# 6P1_EVB.net
KiCad netlist of a schematic drawn in EAGLE
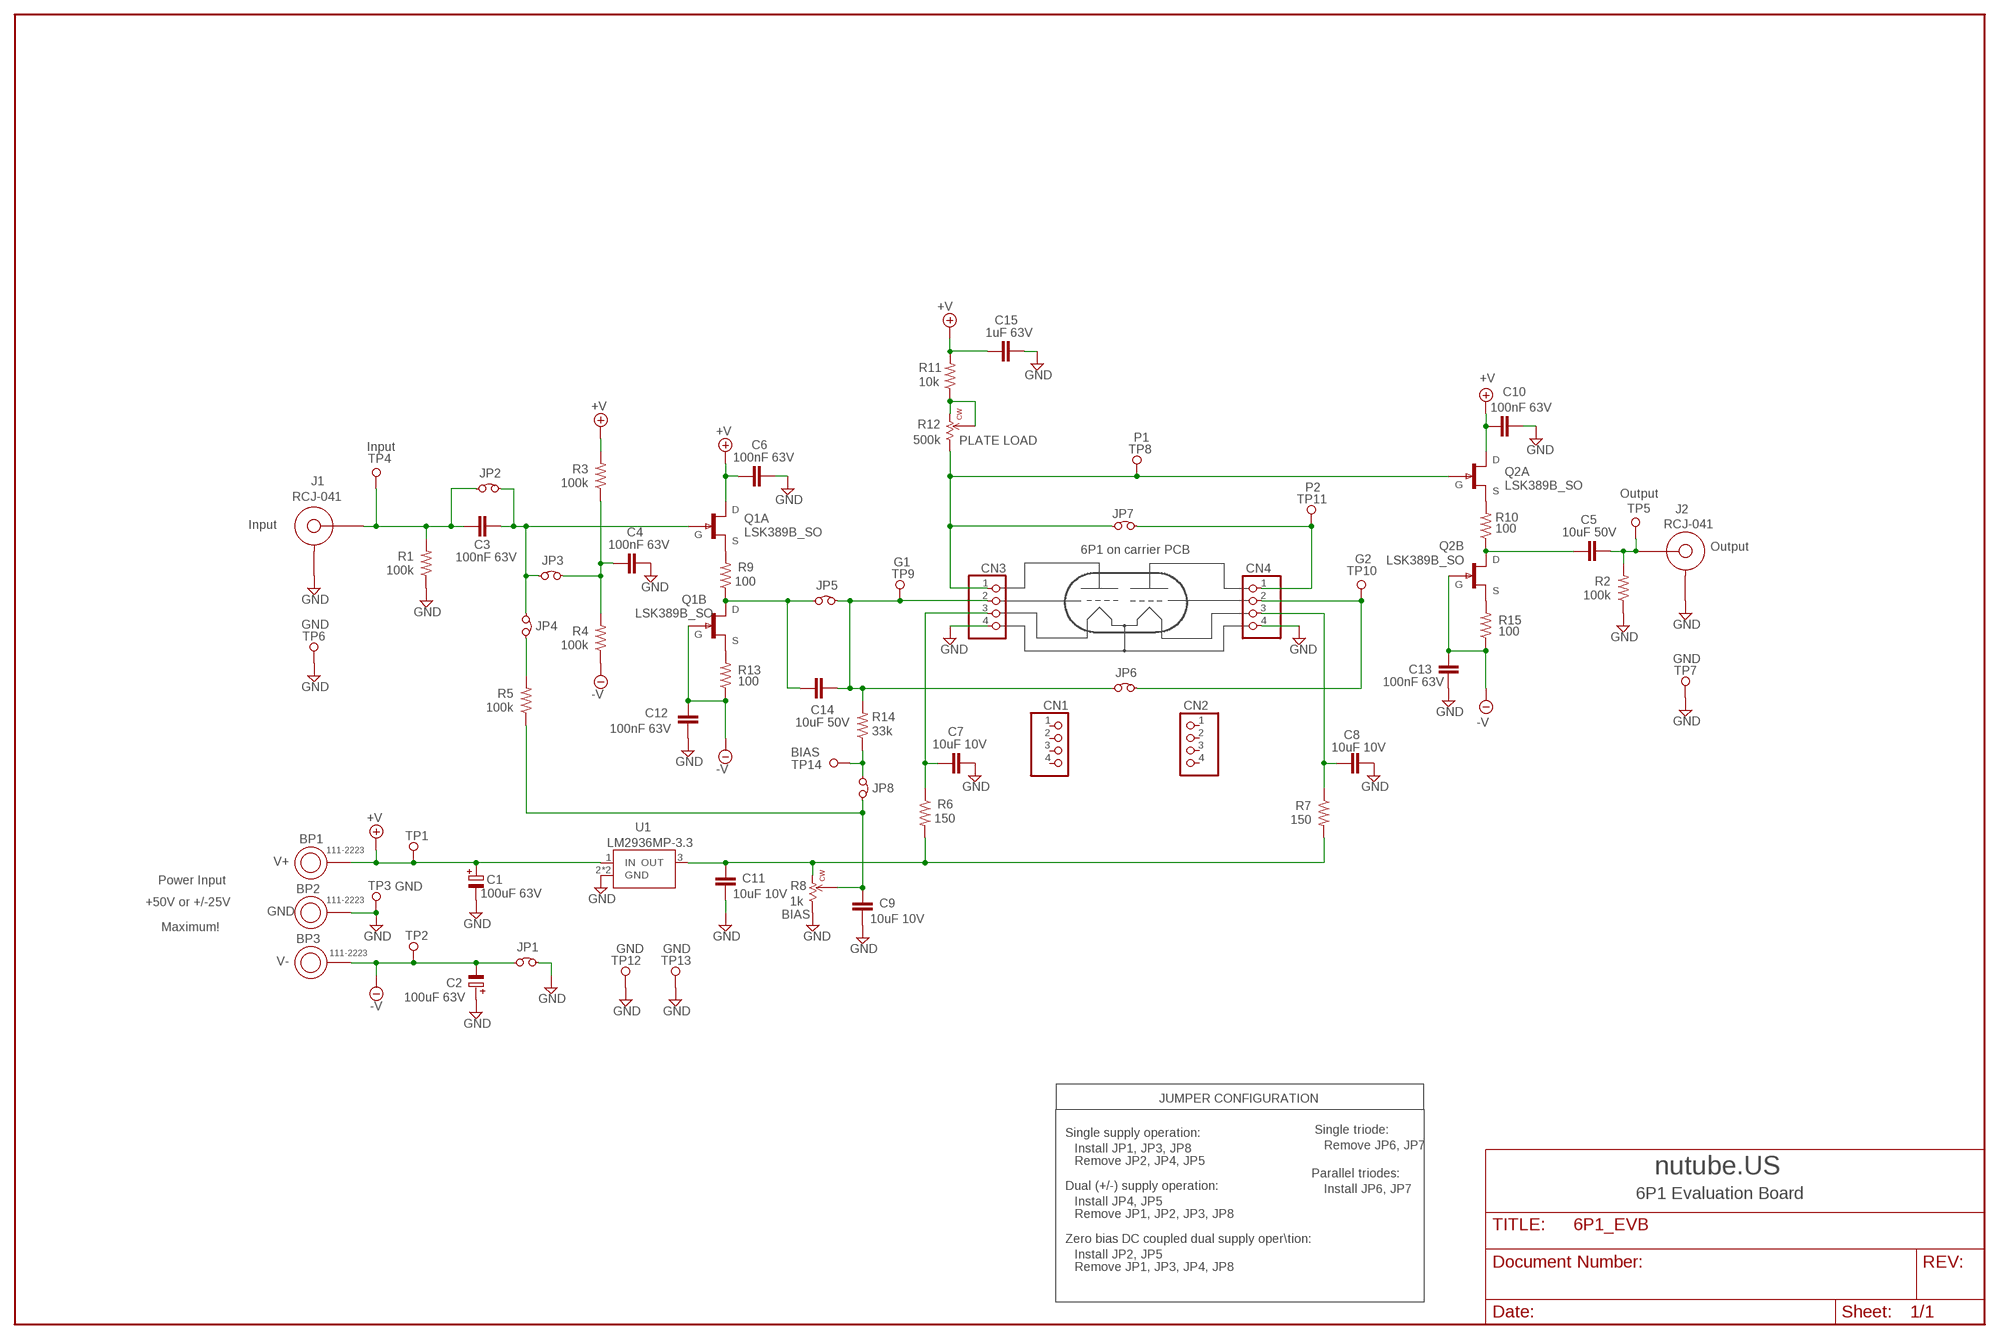
[diagram p0: schematic, sheet 1]

(export (version "E")
  (design (tool "Eeschema 10.0.6"))
  (components
    (comp (ref "BP1")
      (value "111-2223")
      (footprint "eagle-import:BANANA_BP")
      (libsource (lib "eagle-import") (part "BANANA_BP"))
    )
    (comp (ref "BP2")
      (value "111-2223")
      (footprint "eagle-import:BANANA_BP")
      (libsource (lib "eagle-import") (part "BANANA_BP"))
    )
    (comp (ref "BP3")
      (value "111-2223")
      (footprint "eagle-import:BANANA_BP")
      (libsource (lib "eagle-import") (part "BANANA_BP"))
    )
    (comp (ref "C1")
      (value "100uF 63V")
      (footprint "eagle-import:ELCAP_SMT_10MM")
      (libsource (lib "eagle-import") (part "CAP_EL_SMT_10MM"))
    )
    (comp (ref "C2")
      (value "100uF 63V")
      (footprint "eagle-import:ELCAP_SMT_10MM")
      (libsource (lib "eagle-import") (part "CAP_EL_SMT_10MM"))
    )
    (comp (ref "C3")
      (value "100nF 63V")
      (footprint "eagle-import:C050-030X075")
      (libsource (lib "eagle-import") (part "C-EU050-030X075"))
    )
    (comp (ref "C4")
      (value "100nF 63V")
      (footprint "eagle-import:C050-030X075")
      (libsource (lib "eagle-import") (part "C-EU050-030X075"))
    )
    (comp (ref "C5")
      (value "10uF 50V")
      (footprint "eagle-import:C050-110X075")
      (libsource (lib "eagle-import") (part "C-EU050-110X075"))
    )
    (comp (ref "C6")
      (value "100nF 63V")
      (footprint "eagle-import:C050-030X075")
      (libsource (lib "eagle-import") (part "C-EU050-030X075"))
    )
    (comp (ref "C7")
      (value "10uF 10V")
      (footprint "eagle-import:C1206")
      (libsource (lib "eagle-import") (part "C-EUC1206"))
    )
    (comp (ref "C8")
      (value "10uF 10V")
      (footprint "eagle-import:C1206")
      (libsource (lib "eagle-import") (part "C-EUC1206"))
    )
    (comp (ref "C9")
      (value "10uF 10V")
      (footprint "eagle-import:C1206")
      (libsource (lib "eagle-import") (part "C-EUC1206"))
    )
    (comp (ref "C10")
      (value "100nF 63V")
      (footprint "eagle-import:C050-030X075")
      (libsource (lib "eagle-import") (part "C-EU050-030X075"))
    )
    (comp (ref "C11")
      (value "10uF 10V")
      (footprint "eagle-import:C1206")
      (libsource (lib "eagle-import") (part "C-EUC1206"))
    )
    (comp (ref "C12")
      (value "100nF 63V")
      (footprint "eagle-import:C050-030X075")
      (libsource (lib "eagle-import") (part "C-EU050-030X075"))
    )
    (comp (ref "C13")
      (value "100nF 63V")
      (footprint "eagle-import:C050-030X075")
      (libsource (lib "eagle-import") (part "C-EU050-030X075"))
    )
    (comp (ref "C14")
      (value "10uF 50V")
      (footprint "eagle-import:C050-110X075")
      (libsource (lib "eagle-import") (part "C-EU050-110X075"))
    )
    (comp (ref "C15")
      (value "1uF 63V")
      (footprint "eagle-import:C050-050X075")
      (libsource (lib "eagle-import") (part "C-EU050-050X075"))
    )
    (comp (ref "CN1")
      (value "PINHD-1X4")
      (footprint "eagle-import:1X04")
      (libsource (lib "eagle-import") (part "PINHD-1X4"))
    )
    (comp (ref "CN2")
      (value "PINHD-1X4")
      (footprint "eagle-import:1X04")
      (libsource (lib "eagle-import") (part "PINHD-1X4"))
    )
    (comp (ref "CN3")
      (value "PINHD-1X4")
      (footprint "eagle-import:1X04")
      (libsource (lib "eagle-import") (part "PINHD-1X4"))
    )
    (comp (ref "CN4")
      (value "PINHD-1X4")
      (footprint "eagle-import:1X04")
      (libsource (lib "eagle-import") (part "PINHD-1X4"))
    )
    (comp (ref "J1")
      (value "RCJ-041")
      (footprint "eagle-import:JACK_RCA")
      (libsource (lib "eagle-import") (part "JACK_RCA"))
    )
    (comp (ref "J2")
      (value "RCJ-041")
      (footprint "eagle-import:JACK_RCA")
      (libsource (lib "eagle-import") (part "JACK_RCA"))
    )
    (comp (ref "JP1")
      (value "JUMPER")
      (footprint "eagle-import:HDR2X1")
      (libsource (lib "eagle-import") (part "JUMPER"))
    )
    (comp (ref "JP2")
      (value "JUMPER")
      (footprint "eagle-import:HDR2X1")
      (libsource (lib "eagle-import") (part "JUMPER"))
    )
    (comp (ref "JP3")
      (value "JUMPER")
      (footprint "eagle-import:HDR2X1")
      (libsource (lib "eagle-import") (part "JUMPER"))
    )
    (comp (ref "JP4")
      (value "JUMPER")
      (footprint "eagle-import:HDR2X1")
      (libsource (lib "eagle-import") (part "JUMPER"))
    )
    (comp (ref "JP5")
      (value "JUMPER")
      (footprint "eagle-import:HDR2X1")
      (libsource (lib "eagle-import") (part "JUMPER"))
    )
    (comp (ref "JP6")
      (value "JUMPER")
      (footprint "eagle-import:HDR2X1")
      (libsource (lib "eagle-import") (part "JUMPER"))
    )
    (comp (ref "JP7")
      (value "JUMPER")
      (footprint "eagle-import:HDR2X1")
      (libsource (lib "eagle-import") (part "JUMPER"))
    )
    (comp (ref "JP8")
      (value "JUMPER")
      (footprint "eagle-import:HDR2X1")
      (libsource (lib "eagle-import") (part "JUMPER"))
    )
    (comp (ref "Q1")
      (value "LSK389B_SO")
      (footprint "eagle-import:SO8")
      (libsource (lib "eagle-import") (part "LSK389B_SO"))
    )
    (comp (ref "Q2")
      (value "LSK389B_SO")
      (footprint "eagle-import:SO8")
      (libsource (lib "eagle-import") (part "LSK389B_SO"))
    )
    (comp (ref "R1")
      (value "100k")
      (footprint "eagle-import:R0805")
      (libsource (lib "eagle-import") (part "R-US_R0805"))
    )
    (comp (ref "R2")
      (value "100k")
      (footprint "eagle-import:R0805")
      (libsource (lib "eagle-import") (part "R-US_R0805"))
    )
    (comp (ref "R3")
      (value "100k")
      (footprint "eagle-import:R0805")
      (libsource (lib "eagle-import") (part "R-US_R0805"))
    )
    (comp (ref "R4")
      (value "100k")
      (footprint "eagle-import:R0805")
      (libsource (lib "eagle-import") (part "R-US_R0805"))
    )
    (comp (ref "R5")
      (value "100k")
      (footprint "eagle-import:R0805")
      (libsource (lib "eagle-import") (part "R-US_R0805"))
    )
    (comp (ref "R6")
      (value "150")
      (footprint "eagle-import:R0805")
      (libsource (lib "eagle-import") (part "R-US_R0805"))
    )
    (comp (ref "R7")
      (value "150")
      (footprint "eagle-import:R0805")
      (libsource (lib "eagle-import") (part "R-US_R0805"))
    )
    (comp (ref "R8")
      (value "1k")
      (footprint "eagle-import:TRIMPOT_3266")
      (libsource (lib "eagle-import") (part "TRIMPOT_3266"))
    )
    (comp (ref "R9")
      (value "100")
      (footprint "eagle-import:R0805")
      (libsource (lib "eagle-import") (part "R-US_R0805"))
    )
    (comp (ref "R10")
      (value "100")
      (footprint "eagle-import:R0805")
      (libsource (lib "eagle-import") (part "R-US_R0805"))
    )
    (comp (ref "R11")
      (value "10k")
      (footprint "eagle-import:R0805")
      (libsource (lib "eagle-import") (part "R-US_R0805"))
    )
    (comp (ref "R12")
      (value "500k")
      (footprint "eagle-import:TRIMPOT_3266")
      (libsource (lib "eagle-import") (part "TRIMPOT_3266"))
    )
    (comp (ref "R13")
      (value "100")
      (footprint "eagle-import:R0805")
      (libsource (lib "eagle-import") (part "R-US_R0805"))
    )
    (comp (ref "R14")
      (value "33k")
      (footprint "eagle-import:R0805")
      (libsource (lib "eagle-import") (part "R-US_R0805"))
    )
    (comp (ref "R15")
      (value "100")
      (footprint "eagle-import:R0805")
      (libsource (lib "eagle-import") (part "R-US_R0805"))
    )
    (comp (ref "TP1")
      (value "TESTPOINT")
      (footprint "eagle-import:TESTPOINT_63")
      (libsource (lib "eagle-import") (part "TESTPOINT"))
    )
    (comp (ref "TP2")
      (value "TESTPOINT")
      (footprint "eagle-import:TESTPOINT_63")
      (libsource (lib "eagle-import") (part "TESTPOINT"))
    )
    (comp (ref "TP3")
      (value "TESTPOINT")
      (footprint "eagle-import:TESTPOINT_63")
      (libsource (lib "eagle-import") (part "TESTPOINT"))
    )
    (comp (ref "TP4")
      (value "TESTPOINT")
      (footprint "eagle-import:TESTPOINT_63")
      (libsource (lib "eagle-import") (part "TESTPOINT"))
    )
    (comp (ref "TP5")
      (value "TESTPOINT")
      (footprint "eagle-import:TESTPOINT_63")
      (libsource (lib "eagle-import") (part "TESTPOINT"))
    )
    (comp (ref "TP6")
      (value "TESTPOINT")
      (footprint "eagle-import:TESTPOINT_63")
      (libsource (lib "eagle-import") (part "TESTPOINT"))
    )
    (comp (ref "TP7")
      (value "TESTPOINT")
      (footprint "eagle-import:TESTPOINT_63")
      (libsource (lib "eagle-import") (part "TESTPOINT"))
    )
    (comp (ref "TP8")
      (value "TESTPOINT")
      (footprint "eagle-import:TESTPOINT_63")
      (libsource (lib "eagle-import") (part "TESTPOINT"))
    )
    (comp (ref "TP9")
      (value "TESTPOINT")
      (footprint "eagle-import:TESTPOINT_63")
      (libsource (lib "eagle-import") (part "TESTPOINT"))
    )
    (comp (ref "TP10")
      (value "TESTPOINT")
      (footprint "eagle-import:TESTPOINT_63")
      (libsource (lib "eagle-import") (part "TESTPOINT"))
    )
    (comp (ref "TP11")
      (value "TESTPOINT")
      (footprint "eagle-import:TESTPOINT_63")
      (libsource (lib "eagle-import") (part "TESTPOINT"))
    )
    (comp (ref "TP12")
      (value "TESTPOINT")
      (footprint "eagle-import:TESTPOINT_63")
      (libsource (lib "eagle-import") (part "TESTPOINT"))
    )
    (comp (ref "TP13")
      (value "TESTPOINT")
      (footprint "eagle-import:TESTPOINT_63")
      (libsource (lib "eagle-import") (part "TESTPOINT"))
    )
    (comp (ref "TP14")
      (value "TESTPOINT")
      (footprint "eagle-import:TESTPOINT_63")
      (libsource (lib "eagle-import") (part "TESTPOINT"))
    )
    (comp (ref "U1")
      (value "LM2936MP-3.3")
      (footprint "eagle-import:SOT223-3")
      (libsource (lib "eagle-import") (part "LM2940S2"))
    )
  )
  (nets
    (net (code "1") (name "+V") (class "Default")
      (node (ref "BP1") (pin "P$2") (pinfunction "P$1_P$2") (pintype "passive"))
      (node (ref "C1") (pin "P$1") (pinfunction "+_P$1") (pintype "passive"))
      (node (ref "C10") (pin "2") (pinfunction "2_2") (pintype "passive"))
      (node (ref "C15") (pin "2") (pinfunction "2_2") (pintype "passive"))
      (node (ref "C6") (pin "2") (pinfunction "2_2") (pintype "passive"))
      (node (ref "Q1") (pin "2") (pinfunction "D_2") (pintype "passive"))
      (node (ref "Q2") (pin "2") (pinfunction "D_2") (pintype "passive"))
      (node (ref "R11") (pin "2") (pinfunction "2_2") (pintype "passive"))
      (node (ref "R3") (pin "2") (pinfunction "2_2") (pintype "passive"))
      (node (ref "TP1") (pin "P$1") (pinfunction "P$1_P$1") (pintype "passive"))
      (node (ref "U1") (pin "1") (pinfunction "IN_1") (pintype "passive"))
    )
    (net (code "2") (name "-V") (class "Default")
      (node (ref "BP3") (pin "P$2") (pinfunction "P$1_P$2") (pintype "passive"))
      (node (ref "C12") (pin "2") (pinfunction "2_2") (pintype "passive"))
      (node (ref "C13") (pin "2") (pinfunction "2_2") (pintype "passive"))
      (node (ref "C2") (pin "P$2") (pinfunction "-_P$2") (pintype "passive"))
      (node (ref "JP1") (pin "1") (pinfunction "1_1") (pintype "passive"))
      (node (ref "Q1") (pin "8") (pinfunction "G_8") (pintype "passive"))
      (node (ref "Q2") (pin "8") (pinfunction "G_8") (pintype "passive"))
      (node (ref "R13") (pin "1") (pinfunction "1_1") (pintype "passive"))
      (node (ref "R15") (pin "1") (pinfunction "1_1") (pintype "passive"))
      (node (ref "R4") (pin "1") (pinfunction "1_1") (pintype "passive"))
      (node (ref "TP2") (pin "P$1") (pinfunction "P$1_P$1") (pintype "passive"))
    )
    (net (code "3") (name "GND") (class "Default")
      (node (ref "BP2") (pin "P$2") (pinfunction "P$1_P$2") (pintype "passive"))
      (node (ref "C1") (pin "P$2") (pinfunction "-_P$2") (pintype "passive"))
      (node (ref "C10") (pin "1") (pinfunction "1_1") (pintype "passive"))
      (node (ref "C11") (pin "2") (pinfunction "2_2") (pintype "passive"))
      (node (ref "C12") (pin "1") (pinfunction "1_1") (pintype "passive"))
      (node (ref "C13") (pin "1") (pinfunction "1_1") (pintype "passive"))
      (node (ref "C15") (pin "1") (pinfunction "1_1") (pintype "passive"))
      (node (ref "C2") (pin "P$1") (pinfunction "+_P$1") (pintype "passive"))
      (node (ref "C4") (pin "1") (pinfunction "1_1") (pintype "passive"))
      (node (ref "C6") (pin "1") (pinfunction "1_1") (pintype "passive"))
      (node (ref "C7") (pin "2") (pinfunction "2_2") (pintype "passive"))
      (node (ref "C8") (pin "2") (pinfunction "2_2") (pintype "passive"))
      (node (ref "C9") (pin "2") (pinfunction "2_2") (pintype "passive"))
      (node (ref "CN3") (pin "4") (pinfunction "4_4") (pintype "passive"))
      (node (ref "CN4") (pin "4") (pinfunction "4_4") (pintype "passive"))
      (node (ref "J1") (pin "P$1") (pinfunction "3_P$1") (pintype "passive"))
      (node (ref "J2") (pin "P$1") (pinfunction "3_P$1") (pintype "passive"))
      (node (ref "JP1") (pin "2") (pinfunction "2_2") (pintype "passive"))
      (node (ref "R1") (pin "1") (pinfunction "1_1") (pintype "passive"))
      (node (ref "R2") (pin "1") (pinfunction "1_1") (pintype "passive"))
      (node (ref "R8") (pin "1") (pinfunction "1_1") (pintype "passive"))
      (node (ref "TP12") (pin "P$1") (pinfunction "P$1_P$1") (pintype "passive"))
      (node (ref "TP13") (pin "P$1") (pinfunction "P$1_P$1") (pintype "passive"))
      (node (ref "TP3") (pin "P$1") (pinfunction "P$1_P$1") (pintype "passive"))
      (node (ref "TP6") (pin "P$1") (pinfunction "P$1_P$1") (pintype "passive"))
      (node (ref "TP7") (pin "P$1") (pinfunction "P$1_P$1") (pintype "passive"))
      (node (ref "U1") (pin "2") (pinfunction "GND_2") (pintype "passive"))
      (node (ref "U1") (pin "4") (pinfunction "GND_4") (pintype "passive"))
    )
    (net (code "4") (name "Net-(C4-Pad2)") (class "Default")
      (node (ref "C4") (pin "2") (pinfunction "2_2") (pintype "passive"))
      (node (ref "JP3") (pin "2") (pinfunction "2_2") (pintype "passive"))
      (node (ref "R3") (pin "1") (pinfunction "1_1") (pintype "passive"))
      (node (ref "R4") (pin "2") (pinfunction "2_2") (pintype "passive"))
    )
    (net (code "5") (name "Net-(C7-Pad1)") (class "Default")
      (node (ref "C7") (pin "1") (pinfunction "1_1") (pintype "passive"))
      (node (ref "CN3") (pin "3") (pinfunction "3_3") (pintype "passive"))
      (node (ref "R6") (pin "1") (pinfunction "1_1") (pintype "passive"))
    )
    (net (code "6") (name "Net-(C8-Pad1)") (class "Default")
      (node (ref "C8") (pin "1") (pinfunction "1_1") (pintype "passive"))
      (node (ref "CN4") (pin "3") (pinfunction "3_3") (pintype "passive"))
      (node (ref "R7") (pin "1") (pinfunction "1_1") (pintype "passive"))
    )
    (net (code "7") (name "Net-(C9-Pad1)") (class "Default")
      (node (ref "C9") (pin "1") (pinfunction "1_1") (pintype "passive"))
      (node (ref "JP8") (pin "2") (pinfunction "2_2") (pintype "passive"))
      (node (ref "R5") (pin "1") (pinfunction "1_1") (pintype "passive"))
      (node (ref "R8") (pin "2") (pinfunction "2_2") (pintype "passive"))
    )
    (net (code "8") (name "Net-(C14-Pad1)") (class "Default")
      (node (ref "C14") (pin "1") (pinfunction "1_1") (pintype "passive"))
      (node (ref "CN3") (pin "2") (pinfunction "2_2") (pintype "passive"))
      (node (ref "JP5") (pin "2") (pinfunction "2_2") (pintype "passive"))
      (node (ref "JP6") (pin "1") (pinfunction "1_1") (pintype "passive"))
      (node (ref "R14") (pin "2") (pinfunction "2_2") (pintype "passive"))
      (node (ref "TP9") (pin "P$1") (pinfunction "P$1_P$1") (pintype "passive"))
    )
    (net (code "9") (name "Net-(CN4-Pad1)") (class "Default")
      (node (ref "CN4") (pin "1") (pinfunction "1_1") (pintype "passive"))
      (node (ref "JP7") (pin "2") (pinfunction "2_2") (pintype "passive"))
      (node (ref "TP11") (pin "P$1") (pinfunction "P$1_P$1") (pintype "passive"))
    )
    (net (code "10") (name "Net-(CN4-Pad2)") (class "Default")
      (node (ref "CN4") (pin "2") (pinfunction "2_2") (pintype "passive"))
      (node (ref "JP6") (pin "2") (pinfunction "2_2") (pintype "passive"))
      (node (ref "TP10") (pin "P$1") (pinfunction "P$1_P$1") (pintype "passive"))
    )
    (net (code "11") (name "Net-(J1-1)") (class "Default")
      (node (ref "C3") (pin "2") (pinfunction "2_2") (pintype "passive"))
      (node (ref "J1") (pin "P$2") (pinfunction "1_P$2") (pintype "passive"))
      (node (ref "JP2") (pin "1") (pinfunction "1_1") (pintype "passive"))
      (node (ref "R1") (pin "2") (pinfunction "2_2") (pintype "passive"))
      (node (ref "TP4") (pin "P$1") (pinfunction "P$1_P$1") (pintype "passive"))
    )
    (net (code "12") (name "Net-(J2-1)") (class "Default")
      (node (ref "C5") (pin "1") (pinfunction "1_1") (pintype "passive"))
      (node (ref "J2") (pin "P$2") (pinfunction "1_P$2") (pintype "passive"))
      (node (ref "R2") (pin "2") (pinfunction "2_2") (pintype "passive"))
      (node (ref "TP5") (pin "P$1") (pinfunction "P$1_P$1") (pintype "passive"))
    )
    (net (code "13") (name "Net-(JP4-Pad2)") (class "Default")
      (node (ref "JP4") (pin "2") (pinfunction "2_2") (pintype "passive"))
      (node (ref "R5") (pin "2") (pinfunction "2_2") (pintype "passive"))
    )
    (net (code "14") (name "Net-(JP8-Pad1)") (class "Default")
      (node (ref "JP8") (pin "1") (pinfunction "1_1") (pintype "passive"))
      (node (ref "R14") (pin "1") (pinfunction "1_1") (pintype "passive"))
      (node (ref "TP14") (pin "P$1") (pinfunction "P$1_P$1") (pintype "passive"))
    )
    (net (code "15") (name "Net-(Q1A-G)") (class "Default")
      (node (ref "C3") (pin "1") (pinfunction "1_1") (pintype "passive"))
      (node (ref "JP2") (pin "2") (pinfunction "2_2") (pintype "passive"))
      (node (ref "JP3") (pin "1") (pinfunction "1_1") (pintype "passive"))
      (node (ref "JP4") (pin "1") (pinfunction "1_1") (pintype "passive"))
      (node (ref "Q1") (pin "4") (pinfunction "G_4") (pintype "passive"))
    )
    (net (code "16") (name "Net-(Q1A-S)") (class "Default")
      (node (ref "Q1") (pin "1") (pinfunction "S_1") (pintype "passive"))
      (node (ref "R9") (pin "2") (pinfunction "2_2") (pintype "passive"))
    )
    (net (code "17") (name "Net-(Q1B-D)") (class "Default")
      (node (ref "C14") (pin "2") (pinfunction "2_2") (pintype "passive"))
      (node (ref "JP5") (pin "1") (pinfunction "1_1") (pintype "passive"))
      (node (ref "Q1") (pin "6") (pinfunction "D_6") (pintype "passive"))
      (node (ref "R9") (pin "1") (pinfunction "1_1") (pintype "passive"))
    )
    (net (code "18") (name "Net-(Q1B-S)") (class "Default")
      (node (ref "Q1") (pin "5") (pinfunction "S_5") (pintype "passive"))
      (node (ref "R13") (pin "2") (pinfunction "2_2") (pintype "passive"))
    )
    (net (code "19") (name "Net-(Q2A-G)") (class "Default")
      (node (ref "CN3") (pin "1") (pinfunction "1_1") (pintype "passive"))
      (node (ref "JP7") (pin "1") (pinfunction "1_1") (pintype "passive"))
      (node (ref "Q2") (pin "4") (pinfunction "G_4") (pintype "passive"))
      (node (ref "R12") (pin "1") (pinfunction "1_1") (pintype "passive"))
      (node (ref "TP8") (pin "P$1") (pinfunction "P$1_P$1") (pintype "passive"))
    )
    (net (code "20") (name "Net-(Q2A-S)") (class "Default")
      (node (ref "Q2") (pin "1") (pinfunction "S_1") (pintype "passive"))
      (node (ref "R10") (pin "2") (pinfunction "2_2") (pintype "passive"))
    )
    (net (code "21") (name "Net-(Q2B-D)") (class "Default")
      (node (ref "C5") (pin "2") (pinfunction "2_2") (pintype "passive"))
      (node (ref "Q2") (pin "6") (pinfunction "D_6") (pintype "passive"))
      (node (ref "R10") (pin "1") (pinfunction "1_1") (pintype "passive"))
    )
    (net (code "22") (name "Net-(Q2B-S)") (class "Default")
      (node (ref "Q2") (pin "5") (pinfunction "S_5") (pintype "passive"))
      (node (ref "R15") (pin "2") (pinfunction "2_2") (pintype "passive"))
    )
    (net (code "23") (name "Net-(R11-Pad1)") (class "Default")
      (node (ref "R11") (pin "1") (pinfunction "1_1") (pintype "passive"))
      (node (ref "R12") (pin "2") (pinfunction "2_2") (pintype "passive"))
      (node (ref "R12") (pin "3") (pinfunction "3_3") (pintype "passive"))
    )
    (net (code "24") (name "Net-(U1-OUT)") (class "Default")
      (node (ref "C11") (pin "1") (pinfunction "1_1") (pintype "passive"))
      (node (ref "R6") (pin "2") (pinfunction "2_2") (pintype "passive"))
      (node (ref "R7") (pin "2") (pinfunction "2_2") (pintype "passive"))
      (node (ref "R8") (pin "3") (pinfunction "3_3") (pintype "passive"))
      (node (ref "U1") (pin "3") (pinfunction "OUT_3") (pintype "passive"))
    )
    (net (code "25") (name "unconnected-(CN1-Pad1)") (class "Default")
      (node (ref "CN1") (pin "1") (pinfunction "1_1") (pintype "passive"))
    )
    (net (code "26") (name "unconnected-(CN1-Pad2)") (class "Default")
      (node (ref "CN1") (pin "2") (pinfunction "2_2") (pintype "passive"))
    )
    (net (code "27") (name "unconnected-(CN1-Pad3)") (class "Default")
      (node (ref "CN1") (pin "3") (pinfunction "3_3") (pintype "passive"))
    )
    (net (code "28") (name "unconnected-(CN1-Pad4)") (class "Default")
      (node (ref "CN1") (pin "4") (pinfunction "4_4") (pintype "passive"))
    )
    (net (code "29") (name "unconnected-(CN2-Pad1)") (class "Default")
      (node (ref "CN2") (pin "1") (pinfunction "1_1") (pintype "passive"))
    )
    (net (code "30") (name "unconnected-(CN2-Pad2)") (class "Default")
      (node (ref "CN2") (pin "2") (pinfunction "2_2") (pintype "passive"))
    )
    (net (code "31") (name "unconnected-(CN2-Pad3)") (class "Default")
      (node (ref "CN2") (pin "3") (pinfunction "3_3") (pintype "passive"))
    )
    (net (code "32") (name "unconnected-(CN2-Pad4)") (class "Default")
      (node (ref "CN2") (pin "4") (pinfunction "4_4") (pintype "passive"))
    )
  )
)
